# CPU.net
KiCad netlist of a schematic drawn in Altium Designer
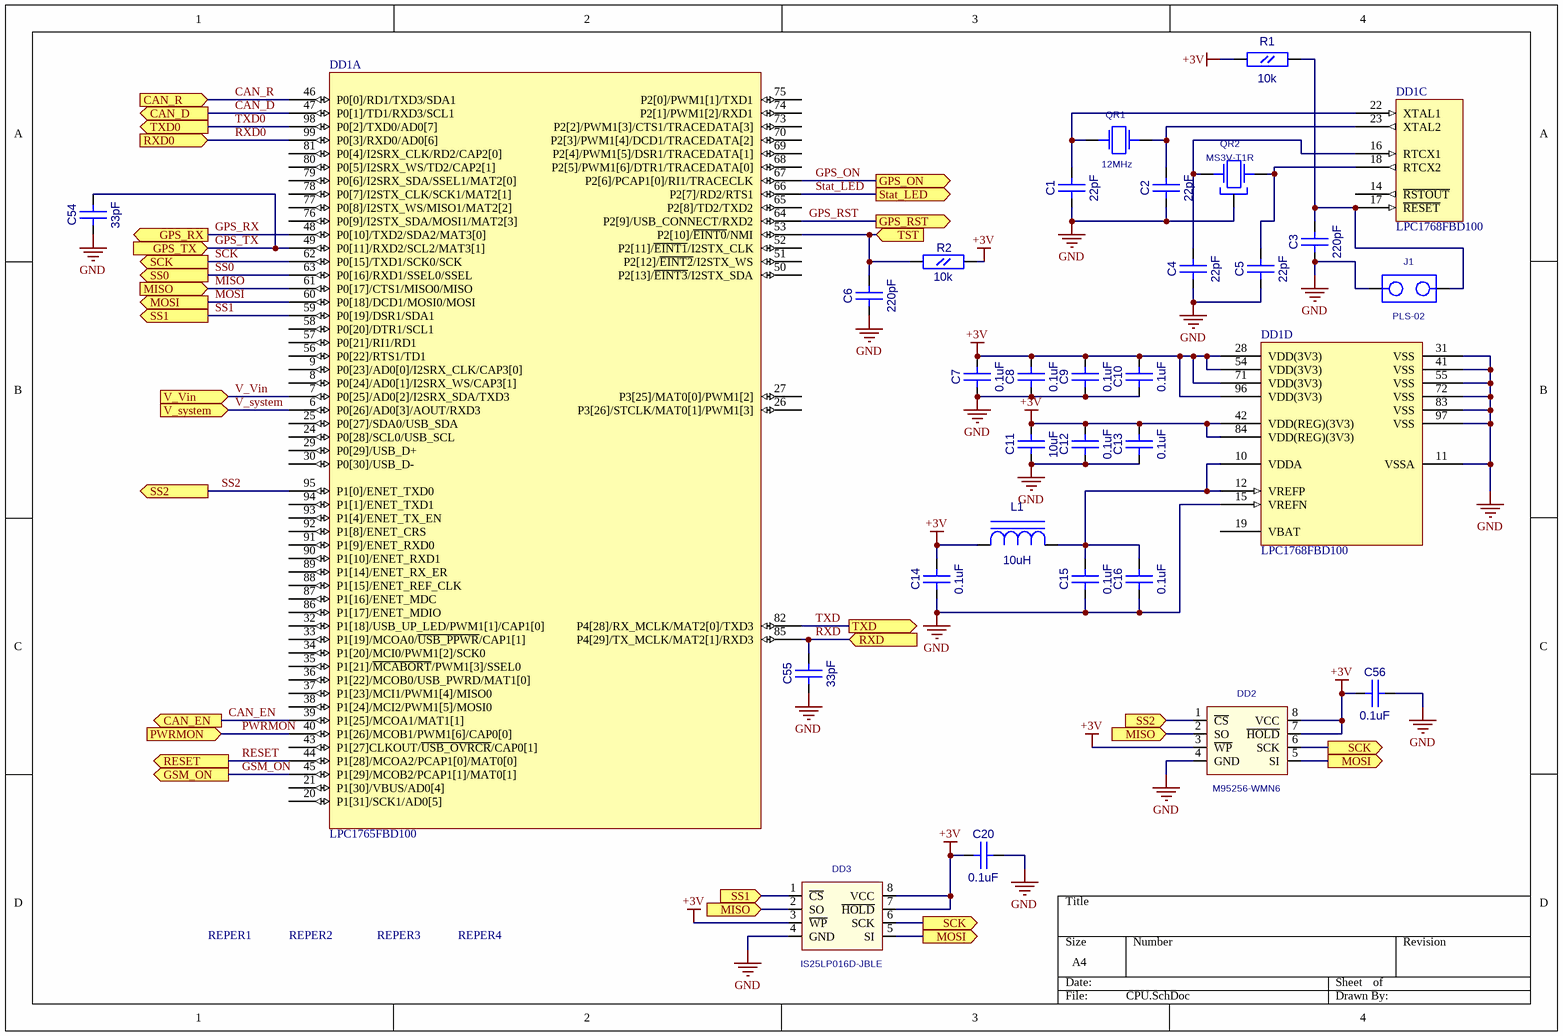
[diagram p0: CPU.SchDoc]

(export (version "E")
  (design (tool "Eeschema 10.0.6"))
  (components
    (comp (ref "C1")
      (value "22pF")
      (footprint "CC0603")
      (description "CC0603")
      (libsource (lib "gprs_modem_2") (part "CC0603"))
    )
    (comp (ref "C2")
      (value "22pF")
      (footprint "CC0603")
      (description "CC0603")
      (libsource (lib "gprs_modem_2") (part "CC0603"))
    )
    (comp (ref "C3")
      (value "220pF")
      (footprint "CC0603")
      (description "CC0603")
      (libsource (lib "gprs_modem_2") (part "CC0603"))
    )
    (comp (ref "C4")
      (value "22pF")
      (footprint "CC0603")
      (description "CC0603")
      (libsource (lib "gprs_modem_2") (part "CC0603"))
    )
    (comp (ref "C5")
      (value "22pF")
      (footprint "CC0603")
      (description "CC0603")
      (libsource (lib "gprs_modem_2") (part "CC0603"))
    )
    (comp (ref "C6")
      (value "220pF")
      (footprint "CC0603")
      (description "CC0603")
      (libsource (lib "gprs_modem_2") (part "CC0603"))
    )
    (comp (ref "C7")
      (value "0.1uF")
      (footprint "CC0603")
      (description "CC0603")
      (libsource (lib "gprs_modem_2") (part "CC0603"))
    )
    (comp (ref "C8")
      (value "0.1uF")
      (footprint "CC0603")
      (description "CC0603")
      (libsource (lib "gprs_modem_2") (part "CC0603"))
    )
    (comp (ref "C9")
      (value "0.1uF")
      (footprint "CC0603")
      (description "CC0603")
      (libsource (lib "gprs_modem_2") (part "CC0603"))
    )
    (comp (ref "C10")
      (value "0.1uF")
      (footprint "CC0603")
      (description "CC0603")
      (libsource (lib "gprs_modem_2") (part "CC0603"))
    )
    (comp (ref "C11")
      (value "10uF")
      (footprint "CC0805")
      (description "CC0805")
      (libsource (lib "gprs_modem_2") (part "CC0805"))
    )
    (comp (ref "C12")
      (value "0.1uF")
      (footprint "CC0603")
      (description "CC0603")
      (libsource (lib "gprs_modem_2") (part "CC0603"))
    )
    (comp (ref "C13")
      (value "0.1uF")
      (footprint "CC0603")
      (description "CC0603")
      (libsource (lib "gprs_modem_2") (part "CC0603"))
    )
    (comp (ref "C14")
      (value "0.1uF")
      (footprint "CC0603")
      (description "CC0603")
      (libsource (lib "gprs_modem_2") (part "CC0603"))
    )
    (comp (ref "C15")
      (value "0.1uF")
      (footprint "CC0603")
      (description "CC0603")
      (libsource (lib "gprs_modem_2") (part "CC0603"))
    )
    (comp (ref "C16")
      (value "0.1uF")
      (footprint "CC0603")
      (description "CC0603")
      (libsource (lib "gprs_modem_2") (part "CC0603"))
    )
    (comp (ref "C20")
      (value "0.1uF")
      (footprint "CC0603")
      (description "CC0603")
      (libsource (lib "gprs_modem_2") (part "CC0603"))
    )
    (comp (ref "C54")
      (value "33pF")
      (footprint "CC0603")
      (description "CC0603")
      (libsource (lib "gprs_modem_2") (part "CC0603"))
    )
    (comp (ref "C55")
      (value "33pF")
      (footprint "CC0603")
      (description "CC0603")
      (libsource (lib "gprs_modem_2") (part "CC0603"))
    )
    (comp (ref "C56")
      (value "0.1uF")
      (footprint "CC0603")
      (description "CC0603")
      (libsource (lib "gprs_modem_2") (part "CC0603"))
    )
    (comp (ref "DD1")
      (value "LPC1765FBD100")
      (footprint "TQFP-100")
      (description "Cortex -M3 32-Bit Microcontroller, 512KB Flash, 64KB RAM, 100-Lead LQFP")
      (libsource (lib "gprs_modem_2") (part "LPC1768FBD100"))
    )
    (comp (ref "DD2")
      (value "M95256-WMN6")
      (footprint "SO-8")
      (description "SPI EEPROM")
      (libsource (lib "gprs_modem_2") (part "M95256-WMN6"))
    )
    (comp (ref "DD3")
      (value "IS25LP016D-JBLE")
      (footprint "EIAJ_SO8")
      (description "S25FL016A0LMFI01")
      (libsource (lib "gprs_modem_2") (part "S25FL016A0LMFI01"))
    )
    (comp (ref "J1") (value "PLS-02") (footprint "PLS-02") (libsource (lib "gprs_modem_2") (part "PLS-02")))
    (comp (ref "L1")
      (value "10uH")
      (footprint "L0603")
      (description "L0603")
      (libsource (lib "gprs_modem_2") (part "L0603"))
    )
    (comp (ref "QR1")
      (value "12MHz")
      (footprint "AC5032_2")
      (description "AC5032/2")
      (libsource (lib "gprs_modem_2") (part "AC5032_2"))
    )
    (comp (ref "QR2")
      (value "MS3V-T1R")
      (footprint "MS3V-T1R")
      (description "CRYSTAL_32768 Hz")
      (libsource (lib "gprs_modem_2") (part "MS3V-T1R"))
    )
    (comp (ref "R1")
      (value "10k")
      (footprint "RC0603")
      (description "RC0603")
      (libsource (lib "gprs_modem_2") (part "RC0603"))
    )
    (comp (ref "R2")
      (value "10k")
      (footprint "RC0603")
      (description "RC0603")
      (libsource (lib "gprs_modem_2") (part "RC0603"))
    )
    (comp (ref "REPER1")
      (value "REPER1.2")
      (footprint "REPER1.2")
      (libsource (lib "gprs_modem") (part "REPER1.2"))
    )
    (comp (ref "REPER2")
      (value "REPER1.2")
      (footprint "REPER1.2")
      (libsource (lib "gprs_modem") (part "REPER1.2"))
    )
    (comp (ref "REPER3")
      (value "REPER1.2")
      (footprint "REPER1.2")
      (libsource (lib "gprs_modem") (part "REPER1.2"))
    )
    (comp (ref "REPER4")
      (value "REPER1.2")
      (footprint "REPER1.2")
      (libsource (lib "gprs_modem") (part "REPER1.2"))
    )
  )
  (nets
    (net (code "1") (name "+3V") (class "Default")
      (node (ref "C10") (pin "2") (pinfunction "B_2") (pintype "passive"))
      (node (ref "C11") (pin "2") (pinfunction "B_2") (pintype "passive"))
      (node (ref "C12") (pin "2") (pinfunction "B_2") (pintype "passive"))
      (node (ref "C13") (pin "2") (pinfunction "B_2") (pintype "passive"))
      (node (ref "C14") (pin "2") (pinfunction "B_2") (pintype "passive"))
      (node (ref "C20") (pin "1") (pinfunction "A_1") (pintype "passive"))
      (node (ref "C56") (pin "1") (pinfunction "A_1") (pintype "passive"))
      (node (ref "C7") (pin "2") (pinfunction "B_2") (pintype "passive"))
      (node (ref "C8") (pin "2") (pinfunction "B_2") (pintype "passive"))
      (node (ref "C9") (pin "2") (pinfunction "B_2") (pintype "passive"))
      (node (ref "DD1") (pin "28") (pinfunction "VDD(3V3)_28") (pintype "power_in"))
      (node (ref "DD1") (pin "42") (pinfunction "VDD(REG)(3V3)_42") (pintype "power_in"))
      (node (ref "DD1") (pin "54") (pinfunction "VDD(3V3)_54") (pintype "power_in"))
      (node (ref "DD1") (pin "71") (pinfunction "VDD(3V3)_71") (pintype "power_in"))
      (node (ref "DD1") (pin "84") (pinfunction "VDD(REG)(3V3)_84") (pintype "power_in"))
      (node (ref "DD1") (pin "96") (pinfunction "VDD(3V3)_96") (pintype "power_in"))
      (node (ref "DD2") (pin "3") (pinfunction "~{WP}_3") (pintype "passive"))
      (node (ref "DD2") (pin "7") (pinfunction "~{HOLD}_7") (pintype "passive"))
      (node (ref "DD2") (pin "8") (pinfunction "VCC_8") (pintype "passive"))
      (node (ref "DD3") (pin "3") (pinfunction "~{WP}_3") (pintype "passive"))
      (node (ref "DD3") (pin "7") (pinfunction "~{HOLD}_7") (pintype "passive"))
      (node (ref "DD3") (pin "8") (pinfunction "VCC_8") (pintype "passive"))
      (node (ref "L1") (pin "1") (pinfunction "A_1") (pintype "passive"))
      (node (ref "R1") (pin "1") (pinfunction "A_1") (pintype "passive"))
      (node (ref "R2") (pin "1") (pinfunction "A_1") (pintype "passive"))
    )
    (net (code "2") (name "/CAN_D") (class "Default")
      (node (ref "DD1") (pin "47") (pinfunction "P0[1]/TD1/RXD3/SCL1_47") (pintype "bidirectional"))
    )
    (net (code "3") (name "/CAN_EN") (class "Default")
      (node (ref "DD1") (pin "39") (pinfunction "P1[25]/MCOA1/MAT1[1]_39") (pintype "bidirectional"))
    )
    (net (code "4") (name "/CAN_R") (class "Default")
      (node (ref "DD1") (pin "46") (pinfunction "P0[0]/RD1/TXD3/SDA1_46") (pintype "bidirectional"))
    )
    (net (code "5") (name "/GPS_ON") (class "Default")
      (node (ref "DD1") (pin "67") (pinfunction "P2[6]/PCAP1[0]/RI1/TRACECLK_67") (pintype "bidirectional"))
    )
    (net (code "6") (name "/GPS_RST") (class "Default")
      (node (ref "DD1") (pin "64") (pinfunction "P2[9]/USB_CONNECT/RXD2_64") (pintype "bidirectional"))
    )
    (net (code "7") (name "/GPS_RX") (class "Default")
      (node (ref "DD1") (pin "48") (pinfunction "P0[10]/TXD2/SDA2/MAT3[0]_48") (pintype "bidirectional"))
    )
    (net (code "8") (name "/GPS_TX") (class "Default")
      (node (ref "C54") (pin "2") (pinfunction "B_2") (pintype "passive"))
      (node (ref "DD1") (pin "49") (pinfunction "P0[11]/RXD2/SCL2/MAT3[1]_49") (pintype "bidirectional"))
    )
    (net (code "9") (name "/GSM_ON") (class "Default")
      (node (ref "DD1") (pin "45") (pinfunction "P1[29]/MCOB2/PCAP1[1]/MAT0[1]_45") (pintype "bidirectional"))
    )
    (net (code "10") (name "/MISO") (class "Default")
      (node (ref "DD1") (pin "61") (pinfunction "P0[17]/CTS1/MISO0/MISO_61") (pintype "bidirectional"))
      (node (ref "DD2") (pin "2") (pinfunction "SO_2") (pintype "passive"))
      (node (ref "DD3") (pin "2") (pinfunction "SO_2") (pintype "passive"))
    )
    (net (code "11") (name "/MOSI") (class "Default")
      (node (ref "DD1") (pin "60") (pinfunction "P0[18]/DCD1/MOSI0/MOSI_60") (pintype "bidirectional"))
      (node (ref "DD2") (pin "5") (pinfunction "SI_5") (pintype "passive"))
      (node (ref "DD3") (pin "5") (pinfunction "SI_5") (pintype "passive"))
    )
    (net (code "12") (name "/PWRMON") (class "Default")
      (node (ref "DD1") (pin "40") (pinfunction "P1[26]/MCOB1/PWM1[6]/CAP0[0]_40") (pintype "bidirectional"))
    )
    (net (code "13") (name "/RESET") (class "Default")
      (node (ref "DD1") (pin "44") (pinfunction "P1[28]/MCOA2/PCAP1[0]/MAT0[0]_44") (pintype "bidirectional"))
    )
    (net (code "14") (name "/RXD") (class "Default")
      (node (ref "C55") (pin "2") (pinfunction "B_2") (pintype "passive"))
      (node (ref "DD1") (pin "85") (pinfunction "P4[29]/TX_MCLK/MAT2[1]/RXD3_85") (pintype "bidirectional"))
    )
    (net (code "15") (name "/RXD0") (class "Default")
      (node (ref "DD1") (pin "99") (pinfunction "P0[3]/RXD0/AD0[6]_99") (pintype "bidirectional"))
    )
    (net (code "16") (name "/SCK") (class "Default")
      (node (ref "DD1") (pin "62") (pinfunction "P0[15]/TXD1/SCK0/SCK_62") (pintype "bidirectional"))
      (node (ref "DD2") (pin "6") (pinfunction "SCK_6") (pintype "passive"))
      (node (ref "DD3") (pin "6") (pinfunction "SCK_6") (pintype "passive"))
    )
    (net (code "17") (name "/SS0") (class "Default")
      (node (ref "DD1") (pin "63") (pinfunction "P0[16]/RXD1/SSEL0/SSEL_63") (pintype "bidirectional"))
    )
    (net (code "18") (name "/SS1") (class "Default")
      (node (ref "DD1") (pin "59") (pinfunction "P0[19]/DSR1/SDA1_59") (pintype "bidirectional"))
      (node (ref "DD3") (pin "1") (pinfunction "~{CS}_1") (pintype "passive"))
    )
    (net (code "19") (name "/SS2") (class "Default")
      (node (ref "DD1") (pin "95") (pinfunction "P1[0]/ENET_TXD0_95") (pintype "bidirectional"))
      (node (ref "DD2") (pin "1") (pinfunction "~{CS}_1") (pintype "passive"))
    )
    (net (code "20") (name "/Stat_LED") (class "Default")
      (node (ref "DD1") (pin "66") (pinfunction "P2[7]/RD2/RTS1_66") (pintype "bidirectional"))
    )
    (net (code "21") (name "/TST") (class "Default")
      (node (ref "C6") (pin "2") (pinfunction "B_2") (pintype "passive"))
      (node (ref "DD1") (pin "53") (pinfunction "P2[10]/~{EINT0}/NMI_53") (pintype "bidirectional"))
      (node (ref "R2") (pin "2") (pinfunction "B_2") (pintype "passive"))
    )
    (net (code "22") (name "/TXD") (class "Default")
      (node (ref "DD1") (pin "82") (pinfunction "P4[28]/RX_MCLK/MAT2[0]/TXD3_82") (pintype "bidirectional"))
    )
    (net (code "23") (name "/TXD0") (class "Default")
      (node (ref "DD1") (pin "98") (pinfunction "P0[2]/TXD0/AD0[7]_98") (pintype "bidirectional"))
    )
    (net (code "24") (name "/V_Vin") (class "Default")
      (node (ref "DD1") (pin "7") (pinfunction "P0[25]/AD0[2]/I2SRX_SDA/TXD3_7") (pintype "bidirectional"))
    )
    (net (code "25") (name "/V_system") (class "Default")
      (node (ref "DD1") (pin "6") (pinfunction "P0[26]/AD0[3]/AOUT/RXD3_6") (pintype "bidirectional"))
    )
    (net (code "26") (name "GND") (class "Default")
      (node (ref "C1") (pin "1") (pinfunction "A_1") (pintype "passive"))
      (node (ref "C10") (pin "1") (pinfunction "A_1") (pintype "passive"))
      (node (ref "C11") (pin "1") (pinfunction "A_1") (pintype "passive"))
      (node (ref "C12") (pin "1") (pinfunction "A_1") (pintype "passive"))
      (node (ref "C13") (pin "1") (pinfunction "A_1") (pintype "passive"))
      (node (ref "C14") (pin "1") (pinfunction "A_1") (pintype "passive"))
      (node (ref "C15") (pin "1") (pinfunction "A_1") (pintype "passive"))
      (node (ref "C16") (pin "1") (pinfunction "A_1") (pintype "passive"))
      (node (ref "C2") (pin "1") (pinfunction "A_1") (pintype "passive"))
      (node (ref "C20") (pin "2") (pinfunction "B_2") (pintype "passive"))
      (node (ref "C3") (pin "1") (pinfunction "A_1") (pintype "passive"))
      (node (ref "C4") (pin "1") (pinfunction "A_1") (pintype "passive"))
      (node (ref "C5") (pin "1") (pinfunction "A_1") (pintype "passive"))
      (node (ref "C54") (pin "1") (pinfunction "A_1") (pintype "passive"))
      (node (ref "C55") (pin "1") (pinfunction "A_1") (pintype "passive"))
      (node (ref "C56") (pin "2") (pinfunction "B_2") (pintype "passive"))
      (node (ref "C6") (pin "1") (pinfunction "A_1") (pintype "passive"))
      (node (ref "C7") (pin "1") (pinfunction "A_1") (pintype "passive"))
      (node (ref "C8") (pin "1") (pinfunction "A_1") (pintype "passive"))
      (node (ref "C9") (pin "1") (pinfunction "A_1") (pintype "passive"))
      (node (ref "DD1") (pin "11") (pinfunction "VSSA_11") (pintype "power_in"))
      (node (ref "DD1") (pin "15") (pinfunction "VREFN_15") (pintype "input"))
      (node (ref "DD1") (pin "31") (pinfunction "VSS_31") (pintype "power_in"))
      (node (ref "DD1") (pin "41") (pinfunction "VSS_41") (pintype "power_in"))
      (node (ref "DD1") (pin "55") (pinfunction "VSS_55") (pintype "power_in"))
      (node (ref "DD1") (pin "72") (pinfunction "VSS_72") (pintype "power_in"))
      (node (ref "DD1") (pin "83") (pinfunction "VSS_83") (pintype "power_in"))
      (node (ref "DD1") (pin "97") (pinfunction "VSS_97") (pintype "power_in"))
      (node (ref "DD2") (pin "4") (pinfunction "GND_4") (pintype "passive"))
      (node (ref "DD3") (pin "4") (pinfunction "GND_4") (pintype "passive"))
      (node (ref "J1") (pin "1") (pintype "passive"))
      (node (ref "QR2") (pin "3") (pinfunction "3_3") (pintype "passive"))
    )
    (net (code "27") (name "Net-(C1-B)") (class "Default")
      (node (ref "C1") (pin "2") (pinfunction "B_2") (pintype "passive"))
      (node (ref "DD1") (pin "22") (pinfunction "XTAL1_22") (pintype "input"))
      (node (ref "QR1") (pin "1") (pintype "passive"))
    )
    (net (code "28") (name "Net-(C2-B)") (class "Default")
      (node (ref "C2") (pin "2") (pinfunction "B_2") (pintype "passive"))
      (node (ref "DD1") (pin "23") (pinfunction "XTAL2_23") (pintype "output"))
      (node (ref "QR1") (pin "2") (pintype "passive"))
    )
    (net (code "29") (name "Net-(C3-B)") (class "Default")
      (node (ref "C3") (pin "2") (pinfunction "B_2") (pintype "passive"))
      (node (ref "DD1") (pin "17") (pinfunction "~{RESET}_17") (pintype "input"))
      (node (ref "J1") (pin "2") (pintype "passive"))
      (node (ref "R1") (pin "2") (pinfunction "B_2") (pintype "passive"))
    )
    (net (code "30") (name "Net-(C4-B)") (class "Default")
      (node (ref "C4") (pin "2") (pinfunction "B_2") (pintype "passive"))
      (node (ref "DD1") (pin "16") (pinfunction "RTCX1_16") (pintype "input"))
      (node (ref "QR2") (pin "2") (pinfunction "X2_2") (pintype "passive"))
    )
    (net (code "31") (name "Net-(C5-B)") (class "Default")
      (node (ref "C5") (pin "2") (pinfunction "B_2") (pintype "passive"))
      (node (ref "DD1") (pin "18") (pinfunction "RTCX2_18") (pintype "output"))
      (node (ref "QR2") (pin "1") (pinfunction "X1_1") (pintype "passive"))
    )
    (net (code "32") (name "Net-(C15-B)") (class "Default")
      (node (ref "C15") (pin "2") (pinfunction "B_2") (pintype "passive"))
      (node (ref "C16") (pin "2") (pinfunction "B_2") (pintype "passive"))
      (node (ref "DD1") (pin "10") (pinfunction "VDDA_10") (pintype "power_in"))
      (node (ref "DD1") (pin "12") (pinfunction "VREFP_12") (pintype "input"))
      (node (ref "L1") (pin "2") (pinfunction "C_2") (pintype "passive"))
    )
    (net (code "33") (name "unconnected-(DD1A-P0[4]{slash}I2SRX_CLK{slash}RD2{slash}CAP2[0]-Pad81)") (class "Default")
      (node (ref "DD1") (pin "81") (pinfunction "P0[4]/I2SRX_CLK/RD2/CAP2[0]_81") (pintype "bidirectional"))
    )
    (net (code "34") (name "unconnected-(DD1A-P0[5]{slash}I2SRX_WS{slash}TD2{slash}CAP2[1]-Pad80)") (class "Default")
      (node (ref "DD1") (pin "80") (pinfunction "P0[5]/I2SRX_WS/TD2/CAP2[1]_80") (pintype "bidirectional"))
    )
    (net (code "35") (name "unconnected-(DD1A-P0[6]{slash}I2SRX_SDA{slash}SSEL1{slash}MAT2[0]-Pad79)") (class "Default")
      (node (ref "DD1") (pin "79") (pinfunction "P0[6]/I2SRX_SDA/SSEL1/MAT2[0]_79") (pintype "bidirectional"))
    )
    (net (code "36") (name "unconnected-(DD1A-P0[7]{slash}I2STX_CLK{slash}SCK1{slash}MAT2[1]-Pad78)") (class "Default")
      (node (ref "DD1") (pin "78") (pinfunction "P0[7]/I2STX_CLK/SCK1/MAT2[1]_78") (pintype "bidirectional"))
    )
    (net (code "37") (name "unconnected-(DD1A-P0[8]{slash}I2STX_WS{slash}MISO1{slash}MAT2[2]-Pad77)") (class "Default")
      (node (ref "DD1") (pin "77") (pinfunction "P0[8]/I2STX_WS/MISO1/MAT2[2]_77") (pintype "bidirectional"))
    )
    (net (code "38") (name "unconnected-(DD1A-P0[9]{slash}I2STX_SDA{slash}MOSI1{slash}MAT2[3]-Pad76)") (class "Default")
      (node (ref "DD1") (pin "76") (pinfunction "P0[9]/I2STX_SDA/MOSI1/MAT2[3]_76") (pintype "bidirectional"))
    )
    (net (code "39") (name "unconnected-(DD1A-P0[20]{slash}DTR1{slash}SCL1-Pad58)") (class "Default")
      (node (ref "DD1") (pin "58") (pinfunction "P0[20]/DTR1/SCL1_58") (pintype "bidirectional"))
    )
    (net (code "40") (name "unconnected-(DD1A-P0[21]{slash}RI1{slash}RD1-Pad57)") (class "Default")
      (node (ref "DD1") (pin "57") (pinfunction "P0[21]/RI1/RD1_57") (pintype "bidirectional"))
    )
    (net (code "41") (name "unconnected-(DD1A-P0[22]{slash}RTS1{slash}TD1-Pad56)") (class "Default")
      (node (ref "DD1") (pin "56") (pinfunction "P0[22]/RTS1/TD1_56") (pintype "bidirectional"))
    )
    (net (code "42") (name "unconnected-(DD1A-P0[23]{slash}AD0[0]{slash}I2SRX_CLK{slash}CAP3[0]-Pad9)") (class "Default")
      (node (ref "DD1") (pin "9") (pinfunction "P0[23]/AD0[0]/I2SRX_CLK/CAP3[0]_9") (pintype "bidirectional"))
    )
    (net (code "43") (name "unconnected-(DD1A-P0[24]{slash}AD0[1]{slash}I2SRX_WS{slash}CAP3[1]-Pad8)") (class "Default")
      (node (ref "DD1") (pin "8") (pinfunction "P0[24]/AD0[1]/I2SRX_WS/CAP3[1]_8") (pintype "bidirectional"))
    )
    (net (code "44") (name "unconnected-(DD1A-P0[27]{slash}SDA0{slash}USB_SDA-Pad25)") (class "Default")
      (node (ref "DD1") (pin "25") (pinfunction "P0[27]/SDA0/USB_SDA_25") (pintype "bidirectional"))
    )
    (net (code "45") (name "unconnected-(DD1A-P0[28]{slash}SCL0{slash}USB_SCL-Pad24)") (class "Default")
      (node (ref "DD1") (pin "24") (pinfunction "P0[28]/SCL0/USB_SCL_24") (pintype "bidirectional"))
    )
    (net (code "46") (name "unconnected-(DD1A-P0[29]{slash}USB_D+-Pad29)") (class "Default")
      (node (ref "DD1") (pin "29") (pinfunction "P0[29]/USB_D+_29") (pintype "bidirectional"))
    )
    (net (code "47") (name "unconnected-(DD1A-P0[30]{slash}USB_D--Pad30)") (class "Default")
      (node (ref "DD1") (pin "30") (pinfunction "P0[30]/USB_D-_30") (pintype "bidirectional"))
    )
    (net (code "48") (name "unconnected-(DD1A-P1[1]{slash}ENET_TXD1-Pad94)") (class "Default")
      (node (ref "DD1") (pin "94") (pinfunction "P1[1]/ENET_TXD1_94") (pintype "bidirectional"))
    )
    (net (code "49") (name "unconnected-(DD1A-P1[4]{slash}ENET_TX_EN-Pad93)") (class "Default")
      (node (ref "DD1") (pin "93") (pinfunction "P1[4]/ENET_TX_EN_93") (pintype "bidirectional"))
    )
    (net (code "50") (name "unconnected-(DD1A-P1[8]{slash}ENET_CRS-Pad92)") (class "Default")
      (node (ref "DD1") (pin "92") (pinfunction "P1[8]/ENET_CRS_92") (pintype "bidirectional"))
    )
    (net (code "51") (name "unconnected-(DD1A-P1[9]{slash}ENET_RXD0-Pad91)") (class "Default")
      (node (ref "DD1") (pin "91") (pinfunction "P1[9]/ENET_RXD0_91") (pintype "bidirectional"))
    )
    (net (code "52") (name "unconnected-(DD1A-P1[10]{slash}ENET_RXD1-Pad90)") (class "Default")
      (node (ref "DD1") (pin "90") (pinfunction "P1[10]/ENET_RXD1_90") (pintype "bidirectional"))
    )
    (net (code "53") (name "unconnected-(DD1A-P1[14]{slash}ENET_RX_ER-Pad89)") (class "Default")
      (node (ref "DD1") (pin "89") (pinfunction "P1[14]/ENET_RX_ER_89") (pintype "bidirectional"))
    )
    (net (code "54") (name "unconnected-(DD1A-P1[15]{slash}ENET_REF_CLK-Pad88)") (class "Default")
      (node (ref "DD1") (pin "88") (pinfunction "P1[15]/ENET_REF_CLK_88") (pintype "bidirectional"))
    )
    (net (code "55") (name "unconnected-(DD1A-P1[16]{slash}ENET_MDC-Pad87)") (class "Default")
      (node (ref "DD1") (pin "87") (pinfunction "P1[16]/ENET_MDC_87") (pintype "bidirectional"))
    )
    (net (code "56") (name "unconnected-(DD1A-P1[17]{slash}ENET_MDIO-Pad86)") (class "Default")
      (node (ref "DD1") (pin "86") (pinfunction "P1[17]/ENET_MDIO_86") (pintype "bidirectional"))
    )
    (net (code "57") (name "unconnected-(DD1A-P1[18]{slash}USB_UP_LED{slash}PWM1[1]{slash}CAP1[0]-Pad32)") (class "Default")
      (node (ref "DD1") (pin "32") (pinfunction "P1[18]/USB_UP_LED/PWM1[1]/CAP1[0]_32") (pintype "bidirectional"))
    )
    (net (code "58") (name "unconnected-(DD1A-P1[19]{slash}MCOA0{slash}~{USB_PPWR}{slash}CAP1[1]-Pad33)") (class "Default")
      (node (ref "DD1") (pin "33") (pinfunction "P1[19]/MCOA0/~{USB_PPWR}/CAP1[1]_33") (pintype "bidirectional"))
    )
    (net (code "59") (name "unconnected-(DD1A-P1[20]{slash}MCI0{slash}PWM1[2]{slash}SCK0-Pad34)") (class "Default")
      (node (ref "DD1") (pin "34") (pinfunction "P1[20]/MCI0/PWM1[2]/SCK0_34") (pintype "bidirectional"))
    )
    (net (code "60") (name "unconnected-(DD1A-P1[21]{slash}~{MCABORT}{slash}PWM1[3]{slash}SSEL0-Pad35)") (class "Default")
      (node (ref "DD1") (pin "35") (pinfunction "P1[21]/~{MCABORT}/PWM1[3]/SSEL0_35") (pintype "bidirectional"))
    )
    (net (code "61") (name "unconnected-(DD1A-P1[22]{slash}MCOB0{slash}USB_PWRD{slash}MAT1[0]-Pad36)") (class "Default")
      (node (ref "DD1") (pin "36") (pinfunction "P1[22]/MCOB0/USB_PWRD/MAT1[0]_36") (pintype "bidirectional"))
    )
    (net (code "62") (name "unconnected-(DD1A-P1[23]{slash}MCI1{slash}PWM1[4]{slash}MISO0-Pad37)") (class "Default")
      (node (ref "DD1") (pin "37") (pinfunction "P1[23]/MCI1/PWM1[4]/MISO0_37") (pintype "bidirectional"))
    )
    (net (code "63") (name "unconnected-(DD1A-P1[24]{slash}MCI2{slash}PWM1[5]{slash}MOSI0-Pad38)") (class "Default")
      (node (ref "DD1") (pin "38") (pinfunction "P1[24]/MCI2/PWM1[5]/MOSI0_38") (pintype "bidirectional"))
    )
    (net (code "64") (name "unconnected-(DD1A-P1[27]CLKOUT{slash}~{USB_OVRCR}{slash}CAP0[1]-Pad43)") (class "Default")
      (node (ref "DD1") (pin "43") (pinfunction "P1[27]CLKOUT/~{USB_OVRCR}/CAP0[1]_43") (pintype "bidirectional"))
    )
    (net (code "65") (name "unconnected-(DD1A-P1[30]{slash}VBUS{slash}AD0[4]-Pad21)") (class "Default")
      (node (ref "DD1") (pin "21") (pinfunction "P1[30]/VBUS/AD0[4]_21") (pintype "bidirectional"))
    )
    (net (code "66") (name "unconnected-(DD1A-P1[31]{slash}SCK1{slash}AD0[5]-Pad20)") (class "Default")
      (node (ref "DD1") (pin "20") (pinfunction "P1[31]/SCK1/AD0[5]_20") (pintype "bidirectional"))
    )
    (net (code "67") (name "unconnected-(DD1A-P2[0]{slash}PWM1[1]{slash}TXD1-Pad75)") (class "Default")
      (node (ref "DD1") (pin "75") (pinfunction "P2[0]/PWM1[1]/TXD1_75") (pintype "bidirectional"))
    )
    (net (code "68") (name "unconnected-(DD1A-P2[1]{slash}PWM1[2]{slash}RXD1-Pad74)") (class "Default")
      (node (ref "DD1") (pin "74") (pinfunction "P2[1]/PWM1[2]/RXD1_74") (pintype "bidirectional"))
    )
    (net (code "69") (name "unconnected-(DD1A-P2[2]{slash}PWM1[3]{slash}CTS1{slash}TRACEDATA[3]-Pad73)") (class "Default")
      (node (ref "DD1") (pin "73") (pinfunction "P2[2]/PWM1[3]/CTS1/TRACEDATA[3]_73") (pintype "bidirectional"))
    )
    (net (code "70") (name "unconnected-(DD1A-P2[3]{slash}PWM1[4]{slash}DCD1{slash}TRACEDATA[2]-Pad70)") (class "Default")
      (node (ref "DD1") (pin "70") (pinfunction "P2[3]/PWM1[4]/DCD1/TRACEDATA[2]_70") (pintype "bidirectional"))
    )
    (net (code "71") (name "unconnected-(DD1A-P2[4]{slash}PWM1[5]{slash}DSR1{slash}TRACEDATA[1]-Pad69)") (class "Default")
      (node (ref "DD1") (pin "69") (pinfunction "P2[4]/PWM1[5]/DSR1/TRACEDATA[1]_69") (pintype "bidirectional"))
    )
    (net (code "72") (name "unconnected-(DD1A-P2[5]{slash}PWM1[6]{slash}DTR1{slash}TRACEDATA[0]-Pad68)") (class "Default")
      (node (ref "DD1") (pin "68") (pinfunction "P2[5]/PWM1[6]/DTR1/TRACEDATA[0]_68") (pintype "bidirectional"))
    )
    (net (code "73") (name "unconnected-(DD1A-P2[8]{slash}TD2{slash}TXD2-Pad65)") (class "Default")
      (node (ref "DD1") (pin "65") (pinfunction "P2[8]/TD2/TXD2_65") (pintype "bidirectional"))
    )
    (net (code "74") (name "unconnected-(DD1A-P2[11]{slash}~{EINT1}{slash}I2STX_CLK-Pad52)") (class "Default")
      (node (ref "DD1") (pin "52") (pinfunction "P2[11]/~{EINT1}/I2STX_CLK_52") (pintype "bidirectional"))
    )
    (net (code "75") (name "unconnected-(DD1A-P2[12]{slash}~{EINT2}{slash}I2STX_WS-Pad51)") (class "Default")
      (node (ref "DD1") (pin "51") (pinfunction "P2[12]/~{EINT2}/I2STX_WS_51") (pintype "bidirectional"))
    )
    (net (code "76") (name "unconnected-(DD1A-P2[13]{slash}~{EINT3}{slash}I2STX_SDA-Pad50)") (class "Default")
      (node (ref "DD1") (pin "50") (pinfunction "P2[13]/~{EINT3}/I2STX_SDA_50") (pintype "bidirectional"))
    )
    (net (code "77") (name "unconnected-(DD1A-P3[25]{slash}MAT0[0]{slash}PWM1[2]-Pad27)") (class "Default")
      (node (ref "DD1") (pin "27") (pinfunction "P3[25]/MAT0[0]/PWM1[2]_27") (pintype "bidirectional"))
    )
    (net (code "78") (name "unconnected-(DD1A-P3[26]{slash}STCLK{slash}MAT0[1]{slash}PWM1[3]-Pad26)") (class "Default")
      (node (ref "DD1") (pin "26") (pinfunction "P3[26]/STCLK/MAT0[1]/PWM1[3]_26") (pintype "bidirectional"))
    )
    (net (code "79") (name "unconnected-(DD1C-~{RSTOUT}-Pad14)") (class "Default")
      (node (ref "DD1") (pin "14") (pinfunction "~{RSTOUT}_14") (pintype "output"))
    )
    (net (code "80") (name "unconnected-(DD1D-VBAT-Pad19)") (class "Default")
      (node (ref "DD1") (pin "19") (pinfunction "VBAT_19") (pintype "power_in"))
    )
    (net (code "81") (name "unconnected-(REPER1-Pad1)") (class "Default")
      (node (ref "REPER1") (pin "1") (pintype "passive"))
    )
    (net (code "82") (name "unconnected-(REPER2-Pad1)") (class "Default")
      (node (ref "REPER2") (pin "1") (pintype "passive"))
    )
    (net (code "83") (name "unconnected-(REPER3-Pad1)") (class "Default")
      (node (ref "REPER3") (pin "1") (pintype "passive"))
    )
    (net (code "84") (name "unconnected-(REPER4-Pad1)") (class "Default")
      (node (ref "REPER4") (pin "1") (pintype "passive"))
    )
  )
)
